# circuit.net
KiCad netlist of a schematic drawn in Altium Designer
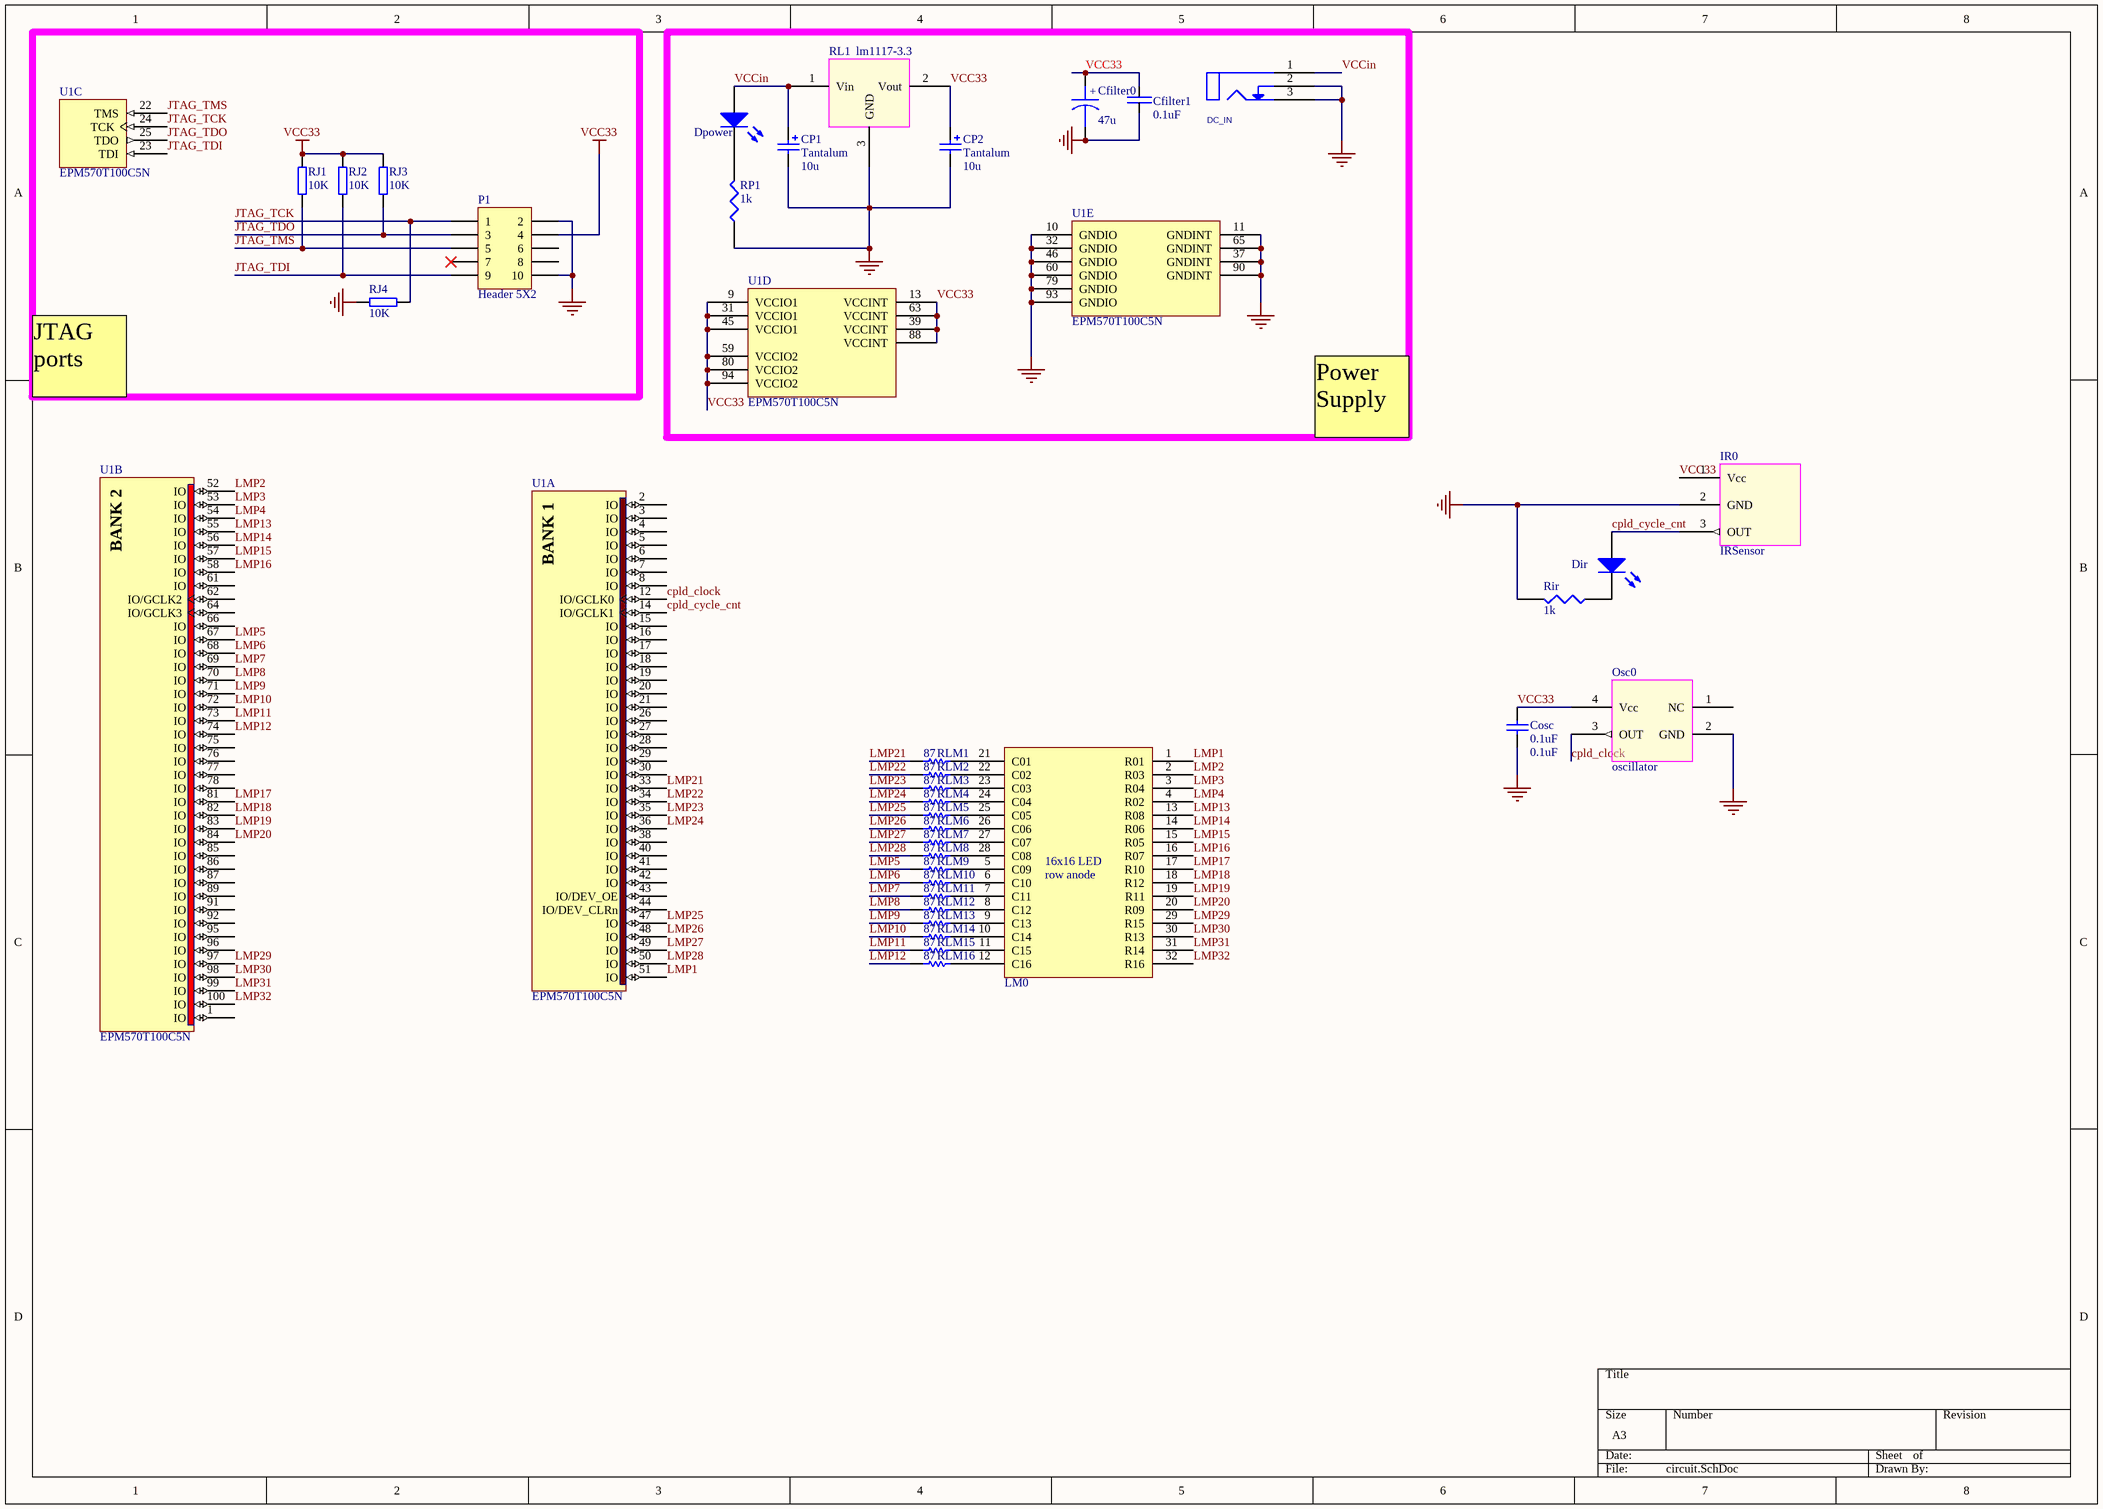
[diagram p0: circuit.SchDoc]

(export (version "E")
  (design (tool "Eeschema 10.0.6"))
  (components
    (comp (ref "Cfilter0")
      (value "47u")
      (footprint "3216C")
      (description "Capacitor")
      (libsource (lib "*") (part "CAPACITOR POL"))
    )
    (comp (ref "Cfilter1")
      (value "0.1uF")
      (footprint "0805")
      (description "Capacitor")
      (libsource (lib "*") (part "CAP"))
    )
    (comp (ref "Cosc")
      (value "0.1uF")
      (footprint "0805")
      (description "Capacitor")
      (fields (field (name "ALTIUM_VALUE") "0.1uF") (field (name "PUBLISHER") "Altium Limited"))
      (libsource (lib "Miscellaneous Devices") (part "Cap"))
    )
    (comp (ref "CP1")
      (value "Tantalum")
      (footprint "3216")
      (description "Polarized Capacitor (Surface Mount)")
      (fields (field (name "ALTIUM_VALUE") "10u") (field (name "PUBLISHER") "Altium Limited"))
      (libsource (lib "Miscellaneous Devices") (part "Cap Pol3"))
    )
    (comp (ref "CP2")
      (value "Tantalum")
      (footprint "3216")
      (description "Polarized Capacitor (Surface Mount)")
      (fields (field (name "ALTIUM_VALUE") "10u") (field (name "PUBLISHER") "Altium Limited"))
      (libsource (lib "Miscellaneous Devices") (part "Cap Pol3"))
    )
    (comp (ref "DC_IN") (value "DC input") (footprint "DC_JACK") (libsource (lib "*") (part "CONN JACK PWR")))
    (comp (ref "Dir")
      (value "LED0")
      (footprint "0805")
      (description "Typical INFRARED GaAs LED")
      (fields (field (name "PUBLISHER") "Altium Limited"))
      (libsource (lib "Miscellaneous Devices") (part "LED0"))
    )
    (comp (ref "Dpower")
      (value "LED0")
      (footprint "0805")
      (description "Typical INFRARED GaAs LED")
      (fields (field (name "PUBLISHER") "Altium Limited"))
      (libsource (lib "Miscellaneous Devices") (part "LED0"))
    )
    (comp (ref "IR0")
      (value "IRSensor")
      (footprint "IRSENSOR_4PIN")
      (libsource (lib "mylib") (part "IRSensor"))
    )
    (comp (ref "LM0")
      (value "LM2256-LEDMat")
      (footprint "LM2256")
      (libsource (lib "mylib") (part "LM2256-LEDMat"))
    )
    (comp (ref "Osc0") (value "oscillator") (footprint "osc1") (libsource (lib "mylib") (part "oscillator")))
    (comp (ref "P1")
      (value "Header 5X2")
      (footprint "IDC10")
      (description "Header, 5-Pin, Dual row")
      (fields (field (name "PUBLISHER") "Altium Limited"))
      (libsource (lib "Miscellaneous Connectors") (part "Header 5X2"))
    )
    (comp (ref "Rir") (value "1k") (footprint "0805") (libsource (lib "Miscellaneous Devices") (part "RES1")))
    (comp (ref "RJ1")
      (value "10K")
      (footprint "0805")
      (libsource (lib "Miscellaneous Devices") (part "RES2"))
    )
    (comp (ref "RJ2")
      (value "10K")
      (footprint "0805")
      (libsource (lib "Miscellaneous Devices") (part "RES2"))
    )
    (comp (ref "RJ3")
      (value "10K")
      (footprint "0805")
      (libsource (lib "Miscellaneous Devices") (part "RES2"))
    )
    (comp (ref "RJ4")
      (value "10K")
      (footprint "0805")
      (libsource (lib "Miscellaneous Devices") (part "RES2"))
    )
    (comp (ref "RL1") (value "lm1117-3.3") (footprint "SOT-223") (libsource (lib "mylib") (part "lm1117")))
    (comp (ref "RLM1")
      (value "87")
      (footprint "0805")
      (description "Resistor")
      (fields (field (name "PUBLISHER") "Altium Limited"))
      (libsource (lib "Miscellaneous Devices") (part "Res1"))
    )
    (comp (ref "RLM2")
      (value "87")
      (footprint "0805")
      (description "Resistor")
      (fields (field (name "PUBLISHER") "Altium Limited"))
      (libsource (lib "Miscellaneous Devices") (part "Res1"))
    )
    (comp (ref "RLM3")
      (value "87")
      (footprint "0805")
      (description "Resistor")
      (fields (field (name "PUBLISHER") "Altium Limited"))
      (libsource (lib "Miscellaneous Devices") (part "Res1"))
    )
    (comp (ref "RLM4")
      (value "87")
      (footprint "0805")
      (description "Resistor")
      (fields (field (name "PUBLISHER") "Altium Limited"))
      (libsource (lib "Miscellaneous Devices") (part "Res1"))
    )
    (comp (ref "RLM5")
      (value "87")
      (footprint "0805")
      (description "Resistor")
      (fields (field (name "PUBLISHER") "Altium Limited"))
      (libsource (lib "Miscellaneous Devices") (part "Res1"))
    )
    (comp (ref "RLM6")
      (value "87")
      (footprint "0805")
      (description "Resistor")
      (fields (field (name "PUBLISHER") "Altium Limited"))
      (libsource (lib "Miscellaneous Devices") (part "Res1"))
    )
    (comp (ref "RLM7")
      (value "87")
      (footprint "0805")
      (description "Resistor")
      (fields (field (name "PUBLISHER") "Altium Limited"))
      (libsource (lib "Miscellaneous Devices") (part "Res1"))
    )
    (comp (ref "RLM8")
      (value "87")
      (footprint "0805")
      (description "Resistor")
      (fields (field (name "PUBLISHER") "Altium Limited"))
      (libsource (lib "Miscellaneous Devices") (part "Res1"))
    )
    (comp (ref "RLM9")
      (value "87")
      (footprint "0805")
      (description "Resistor")
      (fields (field (name "PUBLISHER") "Altium Limited"))
      (libsource (lib "Miscellaneous Devices") (part "Res1"))
    )
    (comp (ref "RLM10")
      (value "87")
      (footprint "0805")
      (description "Resistor")
      (fields (field (name "PUBLISHER") "Altium Limited"))
      (libsource (lib "Miscellaneous Devices") (part "Res1"))
    )
    (comp (ref "RLM11")
      (value "87")
      (footprint "0805")
      (description "Resistor")
      (fields (field (name "PUBLISHER") "Altium Limited"))
      (libsource (lib "Miscellaneous Devices") (part "Res1"))
    )
    (comp (ref "RLM12")
      (value "87")
      (footprint "0805")
      (description "Resistor")
      (fields (field (name "PUBLISHER") "Altium Limited"))
      (libsource (lib "Miscellaneous Devices") (part "Res1"))
    )
    (comp (ref "RLM13")
      (value "87")
      (footprint "0805")
      (description "Resistor")
      (fields (field (name "PUBLISHER") "Altium Limited"))
      (libsource (lib "Miscellaneous Devices") (part "Res1"))
    )
    (comp (ref "RLM14")
      (value "87")
      (footprint "0805")
      (description "Resistor")
      (fields (field (name "PUBLISHER") "Altium Limited"))
      (libsource (lib "Miscellaneous Devices") (part "Res1"))
    )
    (comp (ref "RLM15")
      (value "87")
      (footprint "0805")
      (description "Resistor")
      (fields (field (name "PUBLISHER") "Altium Limited"))
      (libsource (lib "Miscellaneous Devices") (part "Res1"))
    )
    (comp (ref "RLM16")
      (value "87")
      (footprint "0805")
      (description "Resistor")
      (fields (field (name "PUBLISHER") "Altium Limited"))
      (libsource (lib "Miscellaneous Devices") (part "Res1"))
    )
    (comp (ref "RP1") (value "1k") (footprint "0805") (libsource (lib "Miscellaneous Devices") (part "RES1")))
    (comp (ref "U1")
      (value "EPM570T100C5N")
      (footprint "TQFP100_N")
      (fields (field (name "PUBLISHER") "Altium Limited"))
      (libsource (lib "Altera MAX II") (part "EPM570T100C5N"))
    )
  )
  (nets
    (net (code "1") (name "/JTAG_TCK") (class "Default")
      (node (ref "P1") (pin "1") (pinfunction "1_1") (pintype "passive"))
      (node (ref "RJ4") (pin "1") (pinfunction "1_1") (pintype "passive"))
      (node (ref "U1") (pin "24") (pinfunction "TCK_24") (pintype "input"))
    )
    (net (code "2") (name "/JTAG_TDI") (class "Default")
      (node (ref "P1") (pin "9") (pinfunction "9_9") (pintype "passive"))
      (node (ref "RJ2") (pin "2") (pinfunction "2_2") (pintype "passive"))
      (node (ref "U1") (pin "23") (pinfunction "TDI_23") (pintype "input"))
    )
    (net (code "3") (name "/JTAG_TDO") (class "Default")
      (node (ref "P1") (pin "3") (pinfunction "3_3") (pintype "passive"))
      (node (ref "RJ3") (pin "2") (pinfunction "2_2") (pintype "passive"))
      (node (ref "U1") (pin "25") (pinfunction "TDO_25") (pintype "output"))
    )
    (net (code "4") (name "/JTAG_TMS") (class "Default")
      (node (ref "P1") (pin "5") (pinfunction "5_5") (pintype "passive"))
      (node (ref "RJ1") (pin "2") (pinfunction "2_2") (pintype "passive"))
      (node (ref "U1") (pin "22") (pinfunction "TMS_22") (pintype "input"))
    )
    (net (code "5") (name "/LMP1") (class "Default")
      (node (ref "LM0") (pin "1") (pinfunction "R01_1") (pintype "passive"))
      (node (ref "U1") (pin "51") (pinfunction "IO_51") (pintype "bidirectional"))
    )
    (net (code "6") (name "/LMP2") (class "Default")
      (node (ref "LM0") (pin "2") (pinfunction "R03_2") (pintype "passive"))
      (node (ref "U1") (pin "52") (pinfunction "IO_52") (pintype "bidirectional"))
    )
    (net (code "7") (name "/LMP3") (class "Default")
      (node (ref "LM0") (pin "3") (pinfunction "R04_3") (pintype "passive"))
      (node (ref "U1") (pin "53") (pinfunction "IO_53") (pintype "bidirectional"))
    )
    (net (code "8") (name "/LMP4") (class "Default")
      (node (ref "LM0") (pin "4") (pinfunction "R02_4") (pintype "passive"))
      (node (ref "U1") (pin "54") (pinfunction "IO_54") (pintype "bidirectional"))
    )
    (net (code "9") (name "/LMP5") (class "Default")
      (node (ref "RLM9") (pin "1") (pinfunction "1_1") (pintype "passive"))
      (node (ref "U1") (pin "67") (pinfunction "IO_67") (pintype "bidirectional"))
    )
    (net (code "10") (name "/LMP6") (class "Default")
      (node (ref "RLM10") (pin "1") (pinfunction "1_1") (pintype "passive"))
      (node (ref "U1") (pin "68") (pinfunction "IO_68") (pintype "bidirectional"))
    )
    (net (code "11") (name "/LMP7") (class "Default")
      (node (ref "RLM11") (pin "1") (pinfunction "1_1") (pintype "passive"))
      (node (ref "U1") (pin "69") (pinfunction "IO_69") (pintype "bidirectional"))
    )
    (net (code "12") (name "/LMP8") (class "Default")
      (node (ref "RLM12") (pin "1") (pinfunction "1_1") (pintype "passive"))
      (node (ref "U1") (pin "70") (pinfunction "IO_70") (pintype "bidirectional"))
    )
    (net (code "13") (name "/LMP9") (class "Default")
      (node (ref "RLM13") (pin "1") (pinfunction "1_1") (pintype "passive"))
      (node (ref "U1") (pin "71") (pinfunction "IO_71") (pintype "bidirectional"))
    )
    (net (code "14") (name "/LMP10") (class "Default")
      (node (ref "RLM14") (pin "1") (pinfunction "1_1") (pintype "passive"))
      (node (ref "U1") (pin "72") (pinfunction "IO_72") (pintype "bidirectional"))
    )
    (net (code "15") (name "/LMP11") (class "Default")
      (node (ref "RLM15") (pin "1") (pinfunction "1_1") (pintype "passive"))
      (node (ref "U1") (pin "73") (pinfunction "IO_73") (pintype "bidirectional"))
    )
    (net (code "16") (name "/LMP12") (class "Default")
      (node (ref "RLM16") (pin "1") (pinfunction "1_1") (pintype "passive"))
      (node (ref "U1") (pin "74") (pinfunction "IO_74") (pintype "bidirectional"))
    )
    (net (code "17") (name "/LMP13") (class "Default")
      (node (ref "LM0") (pin "13") (pinfunction "R08_13") (pintype "passive"))
      (node (ref "U1") (pin "55") (pinfunction "IO_55") (pintype "bidirectional"))
    )
    (net (code "18") (name "/LMP14") (class "Default")
      (node (ref "LM0") (pin "14") (pinfunction "R06_14") (pintype "passive"))
      (node (ref "U1") (pin "56") (pinfunction "IO_56") (pintype "bidirectional"))
    )
    (net (code "19") (name "/LMP15") (class "Default")
      (node (ref "LM0") (pin "15") (pinfunction "R05_15") (pintype "passive"))
      (node (ref "U1") (pin "57") (pinfunction "IO_57") (pintype "bidirectional"))
    )
    (net (code "20") (name "/LMP16") (class "Default")
      (node (ref "LM0") (pin "16") (pinfunction "R07_16") (pintype "passive"))
      (node (ref "U1") (pin "58") (pinfunction "IO_58") (pintype "bidirectional"))
    )
    (net (code "21") (name "/LMP17") (class "Default")
      (node (ref "LM0") (pin "17") (pinfunction "R10_17") (pintype "passive"))
      (node (ref "U1") (pin "81") (pinfunction "IO_81") (pintype "bidirectional"))
    )
    (net (code "22") (name "/LMP18") (class "Default")
      (node (ref "LM0") (pin "18") (pinfunction "R12_18") (pintype "passive"))
      (node (ref "U1") (pin "82") (pinfunction "IO_82") (pintype "bidirectional"))
    )
    (net (code "23") (name "/LMP19") (class "Default")
      (node (ref "LM0") (pin "19") (pinfunction "R11_19") (pintype "passive"))
      (node (ref "U1") (pin "83") (pinfunction "IO_83") (pintype "bidirectional"))
    )
    (net (code "24") (name "/LMP20") (class "Default")
      (node (ref "LM0") (pin "20") (pinfunction "R09_20") (pintype "passive"))
      (node (ref "U1") (pin "84") (pinfunction "IO_84") (pintype "bidirectional"))
    )
    (net (code "25") (name "/LMP21") (class "Default")
      (node (ref "RLM1") (pin "1") (pinfunction "1_1") (pintype "passive"))
      (node (ref "U1") (pin "33") (pinfunction "IO_33") (pintype "bidirectional"))
    )
    (net (code "26") (name "/LMP22") (class "Default")
      (node (ref "RLM2") (pin "1") (pinfunction "1_1") (pintype "passive"))
      (node (ref "U1") (pin "34") (pinfunction "IO_34") (pintype "bidirectional"))
    )
    (net (code "27") (name "/LMP23") (class "Default")
      (node (ref "RLM3") (pin "1") (pinfunction "1_1") (pintype "passive"))
      (node (ref "U1") (pin "35") (pinfunction "IO_35") (pintype "bidirectional"))
    )
    (net (code "28") (name "/LMP24") (class "Default")
      (node (ref "RLM4") (pin "1") (pinfunction "1_1") (pintype "passive"))
      (node (ref "U1") (pin "36") (pinfunction "IO_36") (pintype "bidirectional"))
    )
    (net (code "29") (name "/LMP25") (class "Default")
      (node (ref "RLM5") (pin "1") (pinfunction "1_1") (pintype "passive"))
      (node (ref "U1") (pin "47") (pinfunction "IO_47") (pintype "bidirectional"))
    )
    (net (code "30") (name "/LMP26") (class "Default")
      (node (ref "RLM6") (pin "1") (pinfunction "1_1") (pintype "passive"))
      (node (ref "U1") (pin "48") (pinfunction "IO_48") (pintype "bidirectional"))
    )
    (net (code "31") (name "/LMP27") (class "Default")
      (node (ref "RLM7") (pin "1") (pinfunction "1_1") (pintype "passive"))
      (node (ref "U1") (pin "49") (pinfunction "IO_49") (pintype "bidirectional"))
    )
    (net (code "32") (name "/LMP28") (class "Default")
      (node (ref "RLM8") (pin "1") (pinfunction "1_1") (pintype "passive"))
      (node (ref "U1") (pin "50") (pinfunction "IO_50") (pintype "bidirectional"))
    )
    (net (code "33") (name "/LMP29") (class "Default")
      (node (ref "LM0") (pin "29") (pinfunction "R15_29") (pintype "passive"))
      (node (ref "U1") (pin "97") (pinfunction "IO_97") (pintype "bidirectional"))
    )
    (net (code "34") (name "/LMP30") (class "Default")
      (node (ref "LM0") (pin "30") (pinfunction "R13_30") (pintype "passive"))
      (node (ref "U1") (pin "98") (pinfunction "IO_98") (pintype "bidirectional"))
    )
    (net (code "35") (name "/LMP31") (class "Default")
      (node (ref "LM0") (pin "31") (pinfunction "R14_31") (pintype "passive"))
      (node (ref "U1") (pin "99") (pinfunction "IO_99") (pintype "bidirectional"))
    )
    (net (code "36") (name "/LMP32") (class "Default")
      (node (ref "LM0") (pin "32") (pinfunction "R16_32") (pintype "passive"))
      (node (ref "U1") (pin "100") (pinfunction "IO_100") (pintype "bidirectional"))
    )
    (net (code "37") (name "/VCCin") (class "Default")
      (node (ref "CP1") (pin "1") (pinfunction "1_1") (pintype "passive"))
      (node (ref "DC_IN") (pin "1") (pinfunction "1_1") (pintype "passive"))
      (node (ref "Dpower") (pin "1") (pinfunction "A_1") (pintype "passive"))
      (node (ref "RL1") (pin "1") (pinfunction "Vin_1") (pintype "passive"))
    )
    (net (code "38") (name "/cpld_clock") (class "Default")
      (node (ref "Osc0") (pin "3") (pinfunction "OUT_3") (pintype "output"))
      (node (ref "U1") (pin "12") (pinfunction "IO/GCLK0_12") (pintype "bidirectional"))
    )
    (net (code "39") (name "/cpld_cycle_cnt") (class "Default")
      (node (ref "Dir") (pin "1") (pinfunction "A_1") (pintype "passive"))
      (node (ref "IR0") (pin "3") (pinfunction "OUT_3") (pintype "output"))
      (node (ref "U1") (pin "14") (pinfunction "IO/GCLK1_14") (pintype "bidirectional"))
    )
    (net (code "40") (name "GND") (class "Default")
      (node (ref "CP1") (pin "2") (pinfunction "2_2") (pintype "passive"))
      (node (ref "CP2") (pin "2") (pinfunction "2_2") (pintype "passive"))
      (node (ref "Cfilter0") (pin "2") (pinfunction "2_2") (pintype "passive"))
      (node (ref "Cfilter1") (pin "2") (pinfunction "2_2") (pintype "passive"))
      (node (ref "Cosc") (pin "1") (pinfunction "1_1") (pintype "passive"))
      (node (ref "DC_IN") (pin "2") (pinfunction "2_2") (pintype "passive"))
      (node (ref "DC_IN") (pin "3") (pinfunction "3_3") (pintype "passive"))
      (node (ref "IR0") (pin "2") (pinfunction "GND_2") (pintype "passive"))
      (node (ref "Osc0") (pin "2") (pinfunction "GND_2") (pintype "passive"))
      (node (ref "P1") (pin "10") (pinfunction "10_10") (pintype "passive"))
      (node (ref "P1") (pin "2") (pinfunction "2_2") (pintype "passive"))
      (node (ref "RJ4") (pin "2") (pinfunction "2_2") (pintype "passive"))
      (node (ref "RL1") (pin "3") (pinfunction "GND_3") (pintype "passive"))
      (node (ref "RP1") (pin "1") (pinfunction "1_1") (pintype "passive"))
      (node (ref "Rir") (pin "2") (pinfunction "2_2") (pintype "passive"))
      (node (ref "U1") (pin "10") (pinfunction "GNDIO_10") (pintype "power_in"))
      (node (ref "U1") (pin "11") (pinfunction "GNDINT_11") (pintype "power_in"))
      (node (ref "U1") (pin "32") (pinfunction "GNDIO_32") (pintype "power_in"))
      (node (ref "U1") (pin "37") (pinfunction "GNDINT_37") (pintype "power_in"))
      (node (ref "U1") (pin "46") (pinfunction "GNDIO_46") (pintype "power_in"))
      (node (ref "U1") (pin "60") (pinfunction "GNDIO_60") (pintype "power_in"))
      (node (ref "U1") (pin "65") (pinfunction "GNDINT_65") (pintype "power_in"))
      (node (ref "U1") (pin "79") (pinfunction "GNDIO_79") (pintype "power_in"))
      (node (ref "U1") (pin "90") (pinfunction "GNDINT_90") (pintype "power_in"))
      (node (ref "U1") (pin "93") (pinfunction "GNDIO_93") (pintype "power_in"))
    )
    (net (code "41") (name "Net-(Dir-K)") (class "Default")
      (node (ref "Dir") (pin "2") (pinfunction "K_2") (pintype "passive"))
      (node (ref "Rir") (pin "1") (pinfunction "1_1") (pintype "passive"))
    )
    (net (code "42") (name "Net-(Dpower-K)") (class "Default")
      (node (ref "Dpower") (pin "2") (pinfunction "K_2") (pintype "passive"))
      (node (ref "RP1") (pin "2") (pinfunction "2_2") (pintype "passive"))
    )
    (net (code "43") (name "Net-(LM0-C01)") (class "Default")
      (node (ref "LM0") (pin "21") (pinfunction "C01_21") (pintype "passive"))
      (node (ref "RLM1") (pin "2") (pinfunction "2_2") (pintype "passive"))
    )
    (net (code "44") (name "Net-(LM0-C02)") (class "Default")
      (node (ref "LM0") (pin "22") (pinfunction "C02_22") (pintype "passive"))
      (node (ref "RLM2") (pin "2") (pinfunction "2_2") (pintype "passive"))
    )
    (net (code "45") (name "Net-(LM0-C03)") (class "Default")
      (node (ref "LM0") (pin "23") (pinfunction "C03_23") (pintype "passive"))
      (node (ref "RLM3") (pin "2") (pinfunction "2_2") (pintype "passive"))
    )
    (net (code "46") (name "Net-(LM0-C04)") (class "Default")
      (node (ref "LM0") (pin "24") (pinfunction "C04_24") (pintype "passive"))
      (node (ref "RLM4") (pin "2") (pinfunction "2_2") (pintype "passive"))
    )
    (net (code "47") (name "Net-(LM0-C05)") (class "Default")
      (node (ref "LM0") (pin "25") (pinfunction "C05_25") (pintype "passive"))
      (node (ref "RLM5") (pin "2") (pinfunction "2_2") (pintype "passive"))
    )
    (net (code "48") (name "Net-(LM0-C06)") (class "Default")
      (node (ref "LM0") (pin "26") (pinfunction "C06_26") (pintype "passive"))
      (node (ref "RLM6") (pin "2") (pinfunction "2_2") (pintype "passive"))
    )
    (net (code "49") (name "Net-(LM0-C07)") (class "Default")
      (node (ref "LM0") (pin "27") (pinfunction "C07_27") (pintype "passive"))
      (node (ref "RLM7") (pin "2") (pinfunction "2_2") (pintype "passive"))
    )
    (net (code "50") (name "Net-(LM0-C08)") (class "Default")
      (node (ref "LM0") (pin "28") (pinfunction "C08_28") (pintype "passive"))
      (node (ref "RLM8") (pin "2") (pinfunction "2_2") (pintype "passive"))
    )
    (net (code "51") (name "Net-(LM0-C09)") (class "Default")
      (node (ref "LM0") (pin "5") (pinfunction "C09_5") (pintype "passive"))
      (node (ref "RLM9") (pin "2") (pinfunction "2_2") (pintype "passive"))
    )
    (net (code "52") (name "Net-(LM0-C10)") (class "Default")
      (node (ref "LM0") (pin "6") (pinfunction "C10_6") (pintype "passive"))
      (node (ref "RLM10") (pin "2") (pinfunction "2_2") (pintype "passive"))
    )
    (net (code "53") (name "Net-(LM0-C11)") (class "Default")
      (node (ref "LM0") (pin "7") (pinfunction "C11_7") (pintype "passive"))
      (node (ref "RLM11") (pin "2") (pinfunction "2_2") (pintype "passive"))
    )
    (net (code "54") (name "Net-(LM0-C12)") (class "Default")
      (node (ref "LM0") (pin "8") (pinfunction "C12_8") (pintype "passive"))
      (node (ref "RLM12") (pin "2") (pinfunction "2_2") (pintype "passive"))
    )
    (net (code "55") (name "Net-(LM0-C13)") (class "Default")
      (node (ref "LM0") (pin "9") (pinfunction "C13_9") (pintype "passive"))
      (node (ref "RLM13") (pin "2") (pinfunction "2_2") (pintype "passive"))
    )
    (net (code "56") (name "Net-(LM0-C14)") (class "Default")
      (node (ref "LM0") (pin "10") (pinfunction "C14_10") (pintype "passive"))
      (node (ref "RLM14") (pin "2") (pinfunction "2_2") (pintype "passive"))
    )
    (net (code "57") (name "Net-(LM0-C15)") (class "Default")
      (node (ref "LM0") (pin "11") (pinfunction "C15_11") (pintype "passive"))
      (node (ref "RLM15") (pin "2") (pinfunction "2_2") (pintype "passive"))
    )
    (net (code "58") (name "Net-(LM0-C16)") (class "Default")
      (node (ref "LM0") (pin "12") (pinfunction "C16_12") (pintype "passive"))
      (node (ref "RLM16") (pin "2") (pinfunction "2_2") (pintype "passive"))
    )
    (net (code "59") (name "VCC33") (class "Default")
      (node (ref "CP2") (pin "1") (pinfunction "1_1") (pintype "passive"))
      (node (ref "Cfilter0") (pin "1") (pinfunction "1_1") (pintype "passive"))
      (node (ref "Cfilter1") (pin "1") (pinfunction "1_1") (pintype "passive"))
      (node (ref "Cosc") (pin "2") (pinfunction "2_2") (pintype "passive"))
      (node (ref "IR0") (pin "1") (pinfunction "Vcc_1") (pintype "passive"))
      (node (ref "Osc0") (pin "4") (pinfunction "Vcc_4") (pintype "passive"))
      (node (ref "P1") (pin "4") (pinfunction "4_4") (pintype "passive"))
      (node (ref "RJ1") (pin "1") (pinfunction "1_1") (pintype "passive"))
      (node (ref "RJ2") (pin "1") (pinfunction "1_1") (pintype "passive"))
      (node (ref "RJ3") (pin "1") (pinfunction "1_1") (pintype "passive"))
      (node (ref "RL1") (pin "2") (pinfunction "Vout_2") (pintype "passive"))
      (node (ref "U1") (pin "13") (pinfunction "VCCINT_13") (pintype "power_in"))
      (node (ref "U1") (pin "31") (pinfunction "VCCIO1_31") (pintype "power_in"))
      (node (ref "U1") (pin "39") (pinfunction "VCCINT_39") (pintype "power_in"))
      (node (ref "U1") (pin "45") (pinfunction "VCCIO1_45") (pintype "power_in"))
      (node (ref "U1") (pin "59") (pinfunction "VCCIO2_59") (pintype "power_in"))
      (node (ref "U1") (pin "63") (pinfunction "VCCINT_63") (pintype "power_in"))
      (node (ref "U1") (pin "80") (pinfunction "VCCIO2_80") (pintype "power_in"))
      (node (ref "U1") (pin "88") (pinfunction "VCCINT_88") (pintype "power_in"))
      (node (ref "U1") (pin "9") (pinfunction "VCCIO1_9") (pintype "power_in"))
      (node (ref "U1") (pin "94") (pinfunction "VCCIO2_94") (pintype "power_in"))
    )
    (net (code "60") (name "unconnected-(IR0-Pad4)") (class "Default")
      (node (ref "IR0") (pin "4") (pinfunction "4_4") (pintype "passive"))
    )
    (net (code "61") (name "unconnected-(Osc0-NC-Pad1)") (class "Default")
      (node (ref "Osc0") (pin "1") (pinfunction "NC_1") (pintype "passive"))
    )
    (net (code "62") (name "unconnected-(P1-Pad6)") (class "Default")
      (node (ref "P1") (pin "6") (pinfunction "6_6") (pintype "passive"))
    )
    (net (code "63") (name "unconnected-(P1-Pad7)") (class "Default")
      (node (ref "P1") (pin "7") (pinfunction "7_7") (pintype "passive+no_connect"))
    )
    (net (code "64") (name "unconnected-(P1-Pad8)") (class "Default")
      (node (ref "P1") (pin "8") (pinfunction "8_8") (pintype "passive"))
    )
    (net (code "65") (name "unconnected-(U1A-IO-Pad2)") (class "Default")
      (node (ref "U1") (pin "2") (pinfunction "IO_2") (pintype "bidirectional"))
    )
    (net (code "66") (name "unconnected-(U1A-IO-Pad3)") (class "Default")
      (node (ref "U1") (pin "3") (pinfunction "IO_3") (pintype "bidirectional"))
    )
    (net (code "67") (name "unconnected-(U1A-IO-Pad4)") (class "Default")
      (node (ref "U1") (pin "4") (pinfunction "IO_4") (pintype "bidirectional"))
    )
    (net (code "68") (name "unconnected-(U1A-IO-Pad5)") (class "Default")
      (node (ref "U1") (pin "5") (pinfunction "IO_5") (pintype "bidirectional"))
    )
    (net (code "69") (name "unconnected-(U1A-IO-Pad6)") (class "Default")
      (node (ref "U1") (pin "6") (pinfunction "IO_6") (pintype "bidirectional"))
    )
    (net (code "70") (name "unconnected-(U1A-IO-Pad7)") (class "Default")
      (node (ref "U1") (pin "7") (pinfunction "IO_7") (pintype "bidirectional"))
    )
    (net (code "71") (name "unconnected-(U1A-IO-Pad8)") (class "Default")
      (node (ref "U1") (pin "8") (pinfunction "IO_8") (pintype "bidirectional"))
    )
    (net (code "72") (name "unconnected-(U1A-IO-Pad15)") (class "Default")
      (node (ref "U1") (pin "15") (pinfunction "IO_15") (pintype "bidirectional"))
    )
    (net (code "73") (name "unconnected-(U1A-IO-Pad16)") (class "Default")
      (node (ref "U1") (pin "16") (pinfunction "IO_16") (pintype "bidirectional"))
    )
    (net (code "74") (name "unconnected-(U1A-IO-Pad17)") (class "Default")
      (node (ref "U1") (pin "17") (pinfunction "IO_17") (pintype "bidirectional"))
    )
    (net (code "75") (name "unconnected-(U1A-IO-Pad18)") (class "Default")
      (node (ref "U1") (pin "18") (pinfunction "IO_18") (pintype "bidirectional"))
    )
    (net (code "76") (name "unconnected-(U1A-IO-Pad19)") (class "Default")
      (node (ref "U1") (pin "19") (pinfunction "IO_19") (pintype "bidirectional"))
    )
    (net (code "77") (name "unconnected-(U1A-IO-Pad20)") (class "Default")
      (node (ref "U1") (pin "20") (pinfunction "IO_20") (pintype "bidirectional"))
    )
    (net (code "78") (name "unconnected-(U1A-IO-Pad21)") (class "Default")
      (node (ref "U1") (pin "21") (pinfunction "IO_21") (pintype "bidirectional"))
    )
    (net (code "79") (name "unconnected-(U1A-IO-Pad26)") (class "Default")
      (node (ref "U1") (pin "26") (pinfunction "IO_26") (pintype "bidirectional"))
    )
    (net (code "80") (name "unconnected-(U1A-IO-Pad27)") (class "Default")
      (node (ref "U1") (pin "27") (pinfunction "IO_27") (pintype "bidirectional"))
    )
    (net (code "81") (name "unconnected-(U1A-IO-Pad28)") (class "Default")
      (node (ref "U1") (pin "28") (pinfunction "IO_28") (pintype "bidirectional"))
    )
    (net (code "82") (name "unconnected-(U1A-IO-Pad29)") (class "Default")
      (node (ref "U1") (pin "29") (pinfunction "IO_29") (pintype "bidirectional"))
    )
    (net (code "83") (name "unconnected-(U1A-IO-Pad30)") (class "Default")
      (node (ref "U1") (pin "30") (pinfunction "IO_30") (pintype "bidirectional"))
    )
    (net (code "84") (name "unconnected-(U1A-IO-Pad38)") (class "Default")
      (node (ref "U1") (pin "38") (pinfunction "IO_38") (pintype "bidirectional"))
    )
    (net (code "85") (name "unconnected-(U1A-IO-Pad40)") (class "Default")
      (node (ref "U1") (pin "40") (pinfunction "IO_40") (pintype "bidirectional"))
    )
    (net (code "86") (name "unconnected-(U1A-IO-Pad41)") (class "Default")
      (node (ref "U1") (pin "41") (pinfunction "IO_41") (pintype "bidirectional"))
    )
    (net (code "87") (name "unconnected-(U1A-IO-Pad42)") (class "Default")
      (node (ref "U1") (pin "42") (pinfunction "IO_42") (pintype "bidirectional"))
    )
    (net (code "88") (name "unconnected-(U1A-IO{slash}DEV_CLRn-Pad44)") (class "Default")
      (node (ref "U1") (pin "44") (pinfunction "IO/DEV_CLRn_44") (pintype "bidirectional"))
    )
    (net (code "89") (name "unconnected-(U1A-IO{slash}DEV_OE-Pad43)") (class "Default")
      (node (ref "U1") (pin "43") (pinfunction "IO/DEV_OE_43") (pintype "bidirectional"))
    )
    (net (code "90") (name "unconnected-(U1B-IO-Pad1)") (class "Default")
      (node (ref "U1") (pin "1") (pinfunction "IO_1") (pintype "bidirectional"))
    )
    (net (code "91") (name "unconnected-(U1B-IO-Pad61)") (class "Default")
      (node (ref "U1") (pin "61") (pinfunction "IO_61") (pintype "bidirectional"))
    )
    (net (code "92") (name "unconnected-(U1B-IO-Pad66)") (class "Default")
      (node (ref "U1") (pin "66") (pinfunction "IO_66") (pintype "bidirectional"))
    )
    (net (code "93") (name "unconnected-(U1B-IO-Pad75)") (class "Default")
      (node (ref "U1") (pin "75") (pinfunction "IO_75") (pintype "bidirectional"))
    )
    (net (code "94") (name "unconnected-(U1B-IO-Pad76)") (class "Default")
      (node (ref "U1") (pin "76") (pinfunction "IO_76") (pintype "bidirectional"))
    )
    (net (code "95") (name "unconnected-(U1B-IO-Pad77)") (class "Default")
      (node (ref "U1") (pin "77") (pinfunction "IO_77") (pintype "bidirectional"))
    )
    (net (code "96") (name "unconnected-(U1B-IO-Pad78)") (class "Default")
      (node (ref "U1") (pin "78") (pinfunction "IO_78") (pintype "bidirectional"))
    )
    (net (code "97") (name "unconnected-(U1B-IO-Pad85)") (class "Default")
      (node (ref "U1") (pin "85") (pinfunction "IO_85") (pintype "bidirectional"))
    )
    (net (code "98") (name "unconnected-(U1B-IO-Pad86)") (class "Default")
      (node (ref "U1") (pin "86") (pinfunction "IO_86") (pintype "bidirectional"))
    )
    (net (code "99") (name "unconnected-(U1B-IO-Pad87)") (class "Default")
      (node (ref "U1") (pin "87") (pinfunction "IO_87") (pintype "bidirectional"))
    )
    (net (code "100") (name "unconnected-(U1B-IO-Pad89)") (class "Default")
      (node (ref "U1") (pin "89") (pinfunction "IO_89") (pintype "bidirectional"))
    )
    (net (code "101") (name "unconnected-(U1B-IO-Pad91)") (class "Default")
      (node (ref "U1") (pin "91") (pinfunction "IO_91") (pintype "bidirectional"))
    )
    (net (code "102") (name "unconnected-(U1B-IO-Pad92)") (class "Default")
      (node (ref "U1") (pin "92") (pinfunction "IO_92") (pintype "bidirectional"))
    )
    (net (code "103") (name "unconnected-(U1B-IO-Pad95)") (class "Default")
      (node (ref "U1") (pin "95") (pinfunction "IO_95") (pintype "bidirectional"))
    )
    (net (code "104") (name "unconnected-(U1B-IO-Pad96)") (class "Default")
      (node (ref "U1") (pin "96") (pinfunction "IO_96") (pintype "bidirectional"))
    )
    (net (code "105") (name "unconnected-(U1B-IO{slash}GCLK2-Pad62)") (class "Default")
      (node (ref "U1") (pin "62") (pinfunction "IO/GCLK2_62") (pintype "bidirectional"))
    )
    (net (code "106") (name "unconnected-(U1B-IO{slash}GCLK3-Pad64)") (class "Default")
      (node (ref "U1") (pin "64") (pinfunction "IO/GCLK3_64") (pintype "bidirectional"))
    )
  )
)
